# I2C_Shield.net
KiCad netlist of a schematic drawn in EAGLE
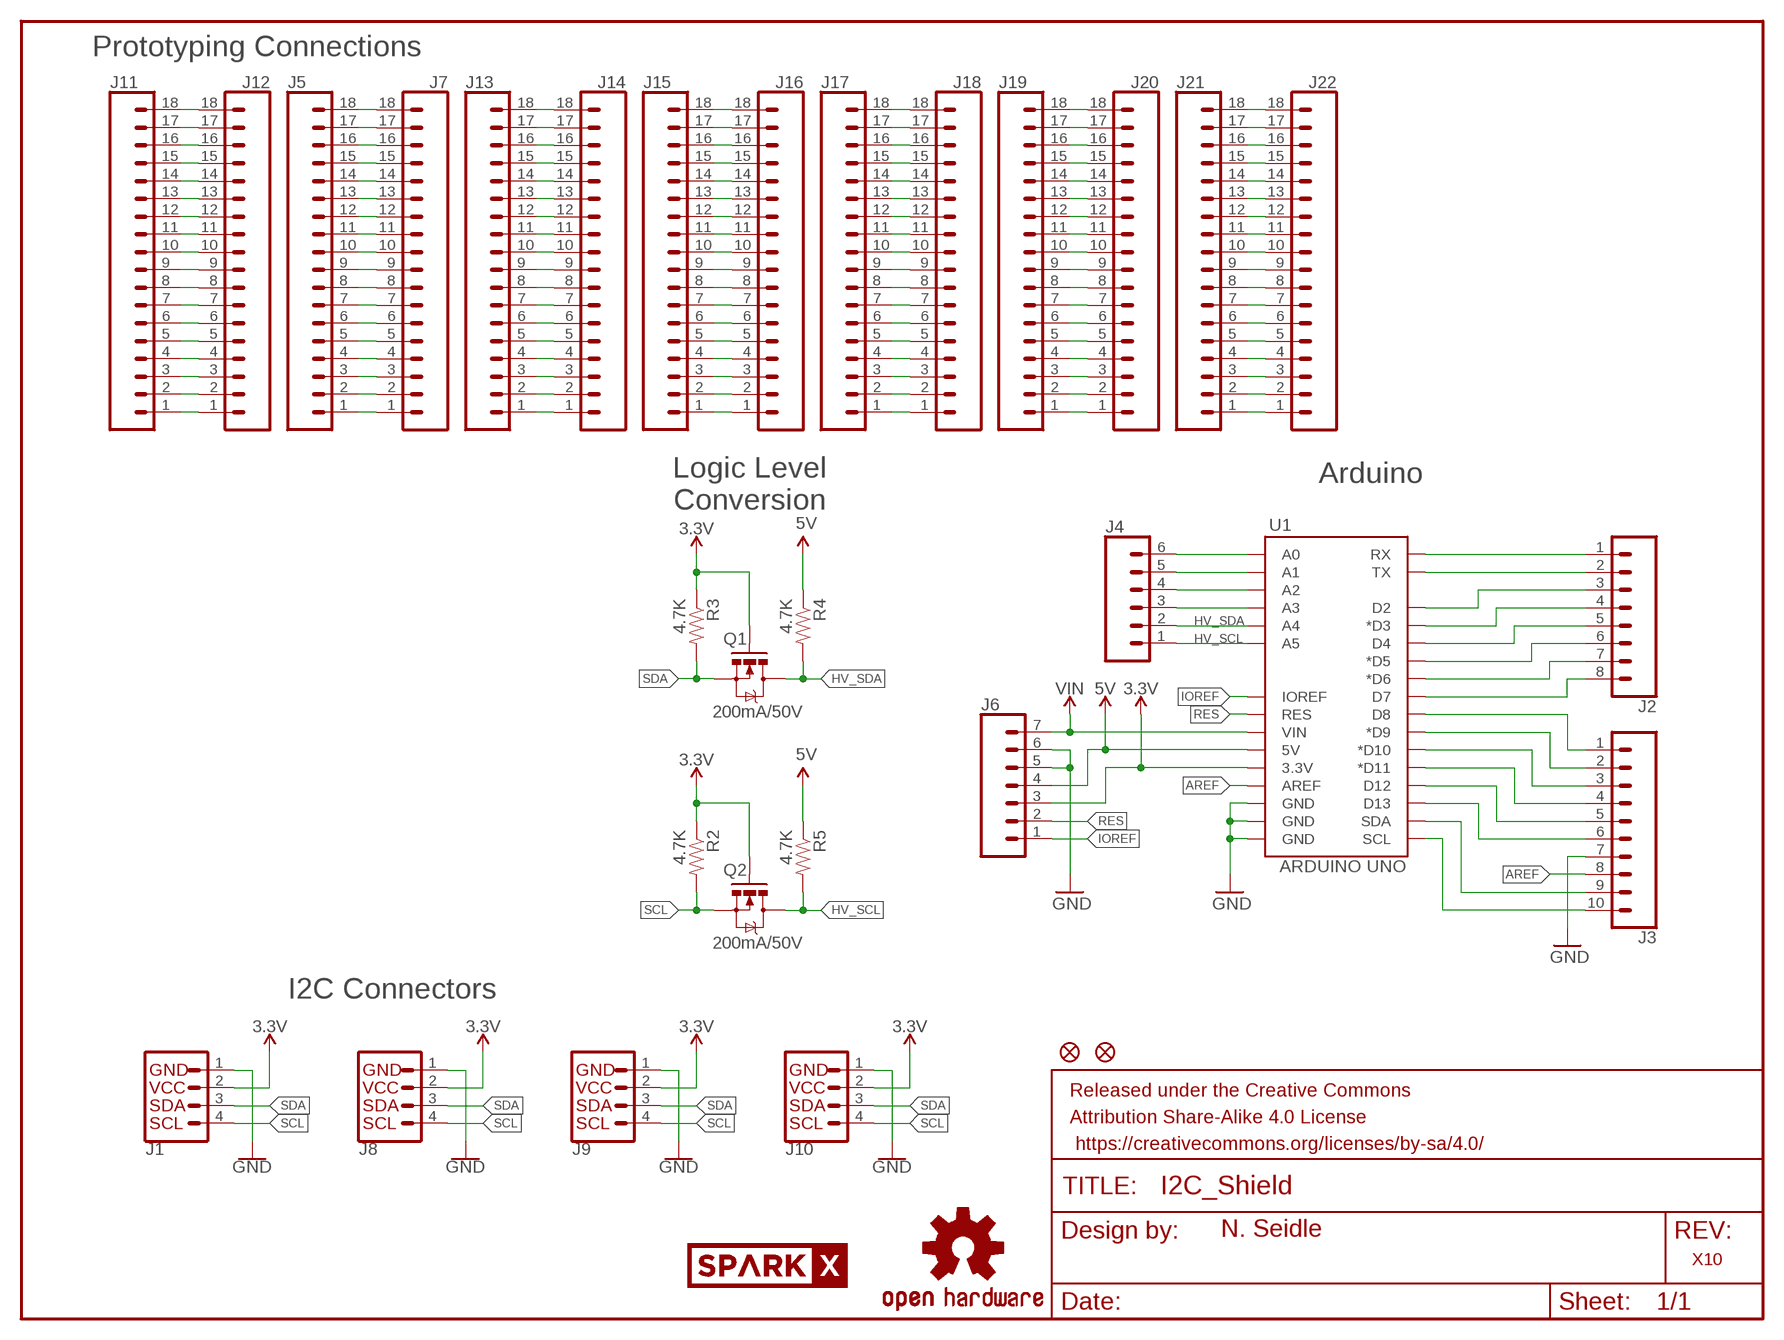
[diagram p0: schematic, sheet 1]

(export (version "E")
  (design (tool "Eeschema 10.0.6"))
  (components
    (comp (ref "FD1")
      (value "FIDUCIAL1X2")
      (footprint "eagle-import:FIDUCIAL-1X2")
      (libsource (lib "eagle-import") (part "FIDUCIAL1X2"))
    )
    (comp (ref "FD2")
      (value "FIDUCIAL1X2")
      (footprint "eagle-import:FIDUCIAL-1X2")
      (libsource (lib "eagle-import") (part "FIDUCIAL1X2"))
    )
    (comp (ref "FRAME1")
      (value "FRAME-LETTER")
      (footprint "eagle-import:CREATIVE_COMMONS")
      (libsource (lib "eagle-import") (part "FRAME-LETTER"))
    )
    (comp (ref "J1")
      (value "I2C_STANDARDJS-1MM")
      (footprint "eagle-import:1X04_1MM_RA")
      (libsource (lib "eagle-import") (part "I2C_STANDARDJS-1MM"))
    )
    (comp (ref "J2")
      (value "CONN_08NO_SILK_FEMALE_PTH")
      (footprint "eagle-import:1X08_NO_SILK")
      (libsource (lib "eagle-import") (part "CONN_08NO_SILK_FEMALE_PTH"))
    )
    (comp (ref "J3")
      (value "CONN_10NO_SILK_PTH_FEMALE")
      (footprint "eagle-import:1X10_NO_SILK")
      (libsource (lib "eagle-import") (part "CONN_10NO_SILK_PTH_FEMALE"))
    )
    (comp (ref "J4")
      (value "CONN_06NO_SILK_FEMALE_PTH")
      (footprint "eagle-import:1X06_NO_SILK")
      (libsource (lib "eagle-import") (part "CONN_06NO_SILK_FEMALE_PTH"))
    )
    (comp (ref "J5")
      (value "CONN_18NO_SILK")
      (footprint "eagle-import:1X18_NO_SILK")
      (libsource (lib "eagle-import") (part "CONN_18NO_SILK"))
    )
    (comp (ref "J6")
      (value "CONN_07NO_SILK")
      (footprint "eagle-import:1X07_NO_SILK")
      (libsource (lib "eagle-import") (part "CONN_07NO_SILK"))
    )
    (comp (ref "J7")
      (value "CONN_18NO_SILK")
      (footprint "eagle-import:1X18_NO_SILK")
      (libsource (lib "eagle-import") (part "CONN_18NO_SILK"))
    )
    (comp (ref "J8")
      (value "I2C_STANDARDJS-1MM")
      (footprint "eagle-import:1X04_1MM_RA")
      (libsource (lib "eagle-import") (part "I2C_STANDARDJS-1MM"))
    )
    (comp (ref "J9")
      (value "I2C_STANDARDJS-1MM")
      (footprint "eagle-import:1X04_1MM_RA")
      (libsource (lib "eagle-import") (part "I2C_STANDARDJS-1MM"))
    )
    (comp (ref "J10")
      (value "I2C_STANDARDJS-1MM")
      (footprint "eagle-import:1X04_1MM_RA")
      (libsource (lib "eagle-import") (part "I2C_STANDARDJS-1MM"))
    )
    (comp (ref "J11")
      (value "CONN_18NO_SILK")
      (footprint "eagle-import:1X18_NO_SILK")
      (libsource (lib "eagle-import") (part "CONN_18NO_SILK"))
    )
    (comp (ref "J12")
      (value "CONN_18NO_SILK")
      (footprint "eagle-import:1X18_NO_SILK")
      (libsource (lib "eagle-import") (part "CONN_18NO_SILK"))
    )
    (comp (ref "J13")
      (value "CONN_18NO_SILK")
      (footprint "eagle-import:1X18_NO_SILK")
      (libsource (lib "eagle-import") (part "CONN_18NO_SILK"))
    )
    (comp (ref "J14")
      (value "CONN_18NO_SILK")
      (footprint "eagle-import:1X18_NO_SILK")
      (libsource (lib "eagle-import") (part "CONN_18NO_SILK"))
    )
    (comp (ref "J15")
      (value "CONN_18NO_SILK")
      (footprint "eagle-import:1X18_NO_SILK")
      (libsource (lib "eagle-import") (part "CONN_18NO_SILK"))
    )
    (comp (ref "J16")
      (value "CONN_18NO_SILK")
      (footprint "eagle-import:1X18_NO_SILK")
      (libsource (lib "eagle-import") (part "CONN_18NO_SILK"))
    )
    (comp (ref "J17")
      (value "CONN_18NO_SILK")
      (footprint "eagle-import:1X18_NO_SILK")
      (libsource (lib "eagle-import") (part "CONN_18NO_SILK"))
    )
    (comp (ref "J18")
      (value "CONN_18NO_SILK")
      (footprint "eagle-import:1X18_NO_SILK")
      (libsource (lib "eagle-import") (part "CONN_18NO_SILK"))
    )
    (comp (ref "J19")
      (value "CONN_18NO_SILK")
      (footprint "eagle-import:1X18_NO_SILK")
      (libsource (lib "eagle-import") (part "CONN_18NO_SILK"))
    )
    (comp (ref "J20")
      (value "CONN_18NO_SILK")
      (footprint "eagle-import:1X18_NO_SILK")
      (libsource (lib "eagle-import") (part "CONN_18NO_SILK"))
    )
    (comp (ref "J21")
      (value "CONN_18NO_SILK")
      (footprint "eagle-import:1X18_NO_SILK")
      (libsource (lib "eagle-import") (part "CONN_18NO_SILK"))
    )
    (comp (ref "J22")
      (value "CONN_18NO_SILK")
      (footprint "eagle-import:1X18_NO_SILK")
      (libsource (lib "eagle-import") (part "CONN_18NO_SILK"))
    )
    (comp (ref "LOGO1")
      (value "OSHW-LOGOMINI")
      (footprint "eagle-import:OSHW-LOGO-MINI")
      (libsource (lib "eagle-import") (part "OSHW-LOGOMINI"))
    )
    (comp (ref "Q1")
      (value "200mA/50V")
      (footprint "eagle-import:SOT23-3")
      (libsource (lib "eagle-import") (part "MOSFET-NCHANNELBSS138"))
    )
    (comp (ref "Q2")
      (value "200mA/50V")
      (footprint "eagle-import:SOT23-3")
      (libsource (lib "eagle-import") (part "MOSFET-NCHANNELBSS138"))
    )
    (comp (ref "R2")
      (value "4.7K")
      (footprint "eagle-import:0603-RES")
      (libsource (lib "eagle-import") (part "4.7KOHM-1/10W-1%(0603)"))
    )
    (comp (ref "R3")
      (value "4.7K")
      (footprint "eagle-import:0603-RES")
      (libsource (lib "eagle-import") (part "4.7KOHM-1/10W-1%(0603)"))
    )
    (comp (ref "R4")
      (value "4.7K")
      (footprint "eagle-import:0603-RES")
      (libsource (lib "eagle-import") (part "4.7KOHM-1/10W-1%(0603)"))
    )
    (comp (ref "R5")
      (value "4.7K")
      (footprint "eagle-import:0603-RES")
      (libsource (lib "eagle-import") (part "4.7KOHM-1/10W-1%(0603)"))
    )
    (comp (ref "U$1")
      (value "SPARKX-LOGO3")
      (footprint "eagle-import:SPARKX-SMALL")
      (libsource (lib "eagle-import") (part "SPARKX-LOGO3"))
    )
    (comp (ref "U$2")
      (value "SPARKX-LOGO5")
      (footprint "eagle-import:SPARKX-LARGE")
      (libsource (lib "eagle-import") (part "SPARKX-LOGO5"))
    )
    (comp (ref "U1")
      (value "ARDUINO UNO")
      (footprint "eagle-import:UNO_R3_SHIELD_NOLABELS")
      (libsource (lib "eagle-import") (part "ARDUINO_R3_SHIELDNOLABELS"))
    )
  )
  (nets
    (net (code "1") (name "3.3V") (class "Default")
      (node (ref "J1") (pin "2") (pinfunction "VCC_2") (pintype "power_in"))
      (node (ref "J10") (pin "2") (pinfunction "VCC_2") (pintype "power_in"))
      (node (ref "J6") (pin "3") (pinfunction "3_3") (pintype "passive"))
      (node (ref "J8") (pin "2") (pinfunction "VCC_2") (pintype "power_in"))
      (node (ref "J9") (pin "2") (pinfunction "VCC_2") (pintype "power_in"))
      (node (ref "Q1") (pin "1") (pinfunction "G_1") (pintype "passive"))
      (node (ref "Q2") (pin "1") (pinfunction "G_1") (pintype "passive"))
      (node (ref "R2") (pin "1") (pinfunction "1_1") (pintype "passive"))
      (node (ref "R3") (pin "1") (pinfunction "1_1") (pintype "passive"))
      (node (ref "U1") (pin "3.3V") (pinfunction "3.3V_3.3V") (pintype "bidirectional"))
    )
    (net (code "2") (name "5V") (class "Default")
      (node (ref "J6") (pin "4") (pinfunction "4_4") (pintype "passive"))
      (node (ref "R4") (pin "1") (pinfunction "1_1") (pintype "passive"))
      (node (ref "R5") (pin "1") (pinfunction "1_1") (pintype "passive"))
      (node (ref "U1") (pin "5V") (pinfunction "5V_5V") (pintype "bidirectional"))
    )
    (net (code "3") (name "AREF") (class "Default")
      (node (ref "J3") (pin "8") (pinfunction "8_8") (pintype "passive"))
      (node (ref "U1") (pin "AREF") (pinfunction "AREF_AREF") (pintype "bidirectional"))
    )
    (net (code "4") (name "GND") (class "Default")
      (node (ref "J1") (pin "1") (pinfunction "GND_1") (pintype "power_in"))
      (node (ref "J10") (pin "1") (pinfunction "GND_1") (pintype "power_in"))
      (node (ref "J3") (pin "7") (pinfunction "7_7") (pintype "passive"))
      (node (ref "J6") (pin "5") (pinfunction "5_5") (pintype "passive"))
      (node (ref "J6") (pin "6") (pinfunction "6_6") (pintype "passive"))
      (node (ref "J8") (pin "1") (pinfunction "GND_1") (pintype "power_in"))
      (node (ref "J9") (pin "1") (pinfunction "GND_1") (pintype "power_in"))
      (node (ref "U1") (pin "GND@0") (pinfunction "GND_GND@0") (pintype "bidirectional"))
      (node (ref "U1") (pin "GND@1") (pinfunction "GND_GND@1") (pintype "bidirectional"))
      (node (ref "U1") (pin "GND@2") (pinfunction "GND_GND@2") (pintype "bidirectional"))
    )
    (net (code "5") (name "HV_SCL") (class "Default")
      (node (ref "J4") (pin "1") (pinfunction "1_1") (pintype "passive"))
      (node (ref "Q2") (pin "3") (pinfunction "D_3") (pintype "passive"))
      (node (ref "R5") (pin "2") (pinfunction "2_2") (pintype "passive"))
      (node (ref "U1") (pin "A5") (pinfunction "A5_A5") (pintype "bidirectional"))
    )
    (net (code "6") (name "HV_SDA") (class "Default")
      (node (ref "J4") (pin "2") (pinfunction "2_2") (pintype "passive"))
      (node (ref "Q1") (pin "3") (pinfunction "D_3") (pintype "passive"))
      (node (ref "R4") (pin "2") (pinfunction "2_2") (pintype "passive"))
      (node (ref "U1") (pin "A4") (pinfunction "A4_A4") (pintype "bidirectional"))
    )
    (net (code "7") (name "IOREF") (class "Default")
      (node (ref "J6") (pin "1") (pinfunction "1_1") (pintype "passive"))
      (node (ref "U1") (pin "IOREF") (pinfunction "IOREF_IOREF") (pintype "bidirectional"))
    )
    (net (code "8") (name "Net-(J2-Pad1)") (class "Default")
      (node (ref "J2") (pin "1") (pinfunction "1_1") (pintype "passive"))
      (node (ref "U1") (pin "RX") (pinfunction "RX_RX") (pintype "bidirectional"))
    )
    (net (code "9") (name "Net-(J2-Pad2)") (class "Default")
      (node (ref "J2") (pin "2") (pinfunction "2_2") (pintype "passive"))
      (node (ref "U1") (pin "TX") (pinfunction "TX_TX") (pintype "bidirectional"))
    )
    (net (code "10") (name "Net-(J2-Pad3)") (class "Default")
      (node (ref "J2") (pin "3") (pinfunction "3_3") (pintype "passive"))
      (node (ref "U1") (pin "D2") (pinfunction "D2_D2") (pintype "bidirectional"))
    )
    (net (code "11") (name "Net-(J2-Pad5)") (class "Default")
      (node (ref "J2") (pin "5") (pinfunction "5_5") (pintype "passive"))
      (node (ref "U1") (pin "D4") (pinfunction "D4_D4") (pintype "bidirectional"))
    )
    (net (code "12") (name "Net-(J2-Pad8)") (class "Default")
      (node (ref "J2") (pin "8") (pinfunction "8_8") (pintype "passive"))
      (node (ref "U1") (pin "D7") (pinfunction "D7_D7") (pintype "bidirectional"))
    )
    (net (code "13") (name "Net-(J3-Pad1)") (class "Default")
      (node (ref "J3") (pin "1") (pinfunction "1_1") (pintype "passive"))
      (node (ref "U1") (pin "D8") (pinfunction "D8_D8") (pintype "bidirectional"))
    )
    (net (code "14") (name "Net-(J3-Pad5)") (class "Default")
      (node (ref "J3") (pin "5") (pinfunction "5_5") (pintype "passive"))
      (node (ref "U1") (pin "D12") (pinfunction "D12_D12") (pintype "bidirectional"))
    )
    (net (code "15") (name "Net-(J3-Pad6)") (class "Default")
      (node (ref "J3") (pin "6") (pinfunction "6_6") (pintype "passive"))
      (node (ref "U1") (pin "D13") (pinfunction "D13_D13") (pintype "bidirectional"))
    )
    (net (code "16") (name "Net-(J3-Pad9)") (class "Default")
      (node (ref "J3") (pin "9") (pinfunction "9_9") (pintype "passive"))
      (node (ref "U1") (pin "SDA") (pinfunction "SDA_SDA") (pintype "bidirectional"))
    )
    (net (code "17") (name "Net-(J3-Pad10)") (class "Default")
      (node (ref "J3") (pin "10") (pinfunction "10_10") (pintype "passive"))
      (node (ref "U1") (pin "SCL") (pinfunction "SCL_SCL") (pintype "bidirectional"))
    )
    (net (code "18") (name "Net-(J4-Pad3)") (class "Default")
      (node (ref "J4") (pin "3") (pinfunction "3_3") (pintype "passive"))
      (node (ref "U1") (pin "A3") (pinfunction "A3_A3") (pintype "bidirectional"))
    )
    (net (code "19") (name "Net-(J4-Pad4)") (class "Default")
      (node (ref "J4") (pin "4") (pinfunction "4_4") (pintype "passive"))
      (node (ref "U1") (pin "A2") (pinfunction "A2_A2") (pintype "bidirectional"))
    )
    (net (code "20") (name "Net-(J4-Pad5)") (class "Default")
      (node (ref "J4") (pin "5") (pinfunction "5_5") (pintype "passive"))
      (node (ref "U1") (pin "A1") (pinfunction "A1_A1") (pintype "bidirectional"))
    )
    (net (code "21") (name "Net-(J4-Pad6)") (class "Default")
      (node (ref "J4") (pin "6") (pinfunction "6_6") (pintype "passive"))
      (node (ref "U1") (pin "A0") (pinfunction "A0_A0") (pintype "bidirectional"))
    )
    (net (code "22") (name "Net-(J5-Pad1)") (class "Default")
      (node (ref "J5") (pin "1") (pinfunction "1_1") (pintype "passive"))
      (node (ref "J7") (pin "1") (pinfunction "1_1") (pintype "passive"))
    )
    (net (code "23") (name "Net-(J5-Pad2)") (class "Default")
      (node (ref "J5") (pin "2") (pinfunction "2_2") (pintype "passive"))
      (node (ref "J7") (pin "2") (pinfunction "2_2") (pintype "passive"))
    )
    (net (code "24") (name "Net-(J5-Pad3)") (class "Default")
      (node (ref "J5") (pin "3") (pinfunction "3_3") (pintype "passive"))
      (node (ref "J7") (pin "3") (pinfunction "3_3") (pintype "passive"))
    )
    (net (code "25") (name "Net-(J5-Pad4)") (class "Default")
      (node (ref "J5") (pin "4") (pinfunction "4_4") (pintype "passive"))
      (node (ref "J7") (pin "4") (pinfunction "4_4") (pintype "passive"))
    )
    (net (code "26") (name "Net-(J5-Pad5)") (class "Default")
      (node (ref "J5") (pin "5") (pinfunction "5_5") (pintype "passive"))
      (node (ref "J7") (pin "5") (pinfunction "5_5") (pintype "passive"))
    )
    (net (code "27") (name "Net-(J5-Pad6)") (class "Default")
      (node (ref "J5") (pin "6") (pinfunction "6_6") (pintype "passive"))
      (node (ref "J7") (pin "6") (pinfunction "6_6") (pintype "passive"))
    )
    (net (code "28") (name "Net-(J5-Pad7)") (class "Default")
      (node (ref "J5") (pin "7") (pinfunction "7_7") (pintype "passive"))
      (node (ref "J7") (pin "7") (pinfunction "7_7") (pintype "passive"))
    )
    (net (code "29") (name "Net-(J5-Pad8)") (class "Default")
      (node (ref "J5") (pin "8") (pinfunction "8_8") (pintype "passive"))
      (node (ref "J7") (pin "8") (pinfunction "8_8") (pintype "passive"))
    )
    (net (code "30") (name "Net-(J5-Pad9)") (class "Default")
      (node (ref "J5") (pin "9") (pinfunction "9_9") (pintype "passive"))
      (node (ref "J7") (pin "9") (pinfunction "9_9") (pintype "passive"))
    )
    (net (code "31") (name "Net-(J5-Pad10)") (class "Default")
      (node (ref "J5") (pin "10") (pinfunction "10_10") (pintype "passive"))
      (node (ref "J7") (pin "10") (pinfunction "10_10") (pintype "passive"))
    )
    (net (code "32") (name "Net-(J5-Pad11)") (class "Default")
      (node (ref "J5") (pin "11") (pinfunction "11_11") (pintype "passive"))
      (node (ref "J7") (pin "11") (pinfunction "11_11") (pintype "passive"))
    )
    (net (code "33") (name "Net-(J5-Pad12)") (class "Default")
      (node (ref "J5") (pin "12") (pinfunction "12_12") (pintype "passive"))
      (node (ref "J7") (pin "12") (pinfunction "12_12") (pintype "passive"))
    )
    (net (code "34") (name "Net-(J5-Pad13)") (class "Default")
      (node (ref "J5") (pin "13") (pinfunction "13_13") (pintype "passive"))
      (node (ref "J7") (pin "13") (pinfunction "13_13") (pintype "passive"))
    )
    (net (code "35") (name "Net-(J5-Pad14)") (class "Default")
      (node (ref "J5") (pin "14") (pinfunction "14_14") (pintype "passive"))
      (node (ref "J7") (pin "14") (pinfunction "14_14") (pintype "passive"))
    )
    (net (code "36") (name "Net-(J5-Pad15)") (class "Default")
      (node (ref "J5") (pin "15") (pinfunction "15_15") (pintype "passive"))
      (node (ref "J7") (pin "15") (pinfunction "15_15") (pintype "passive"))
    )
    (net (code "37") (name "Net-(J5-Pad16)") (class "Default")
      (node (ref "J5") (pin "16") (pinfunction "16_16") (pintype "passive"))
      (node (ref "J7") (pin "16") (pinfunction "16_16") (pintype "passive"))
    )
    (net (code "38") (name "Net-(J5-Pad17)") (class "Default")
      (node (ref "J5") (pin "17") (pinfunction "17_17") (pintype "passive"))
      (node (ref "J7") (pin "17") (pinfunction "17_17") (pintype "passive"))
    )
    (net (code "39") (name "Net-(J5-Pad18)") (class "Default")
      (node (ref "J5") (pin "18") (pinfunction "18_18") (pintype "passive"))
      (node (ref "J7") (pin "18") (pinfunction "18_18") (pintype "passive"))
    )
    (net (code "40") (name "Net-(J11-Pad1)") (class "Default")
      (node (ref "J11") (pin "1") (pinfunction "1_1") (pintype "passive"))
      (node (ref "J12") (pin "1") (pinfunction "1_1") (pintype "passive"))
    )
    (net (code "41") (name "Net-(J11-Pad2)") (class "Default")
      (node (ref "J11") (pin "2") (pinfunction "2_2") (pintype "passive"))
      (node (ref "J12") (pin "2") (pinfunction "2_2") (pintype "passive"))
    )
    (net (code "42") (name "Net-(J11-Pad3)") (class "Default")
      (node (ref "J11") (pin "3") (pinfunction "3_3") (pintype "passive"))
      (node (ref "J12") (pin "3") (pinfunction "3_3") (pintype "passive"))
    )
    (net (code "43") (name "Net-(J11-Pad4)") (class "Default")
      (node (ref "J11") (pin "4") (pinfunction "4_4") (pintype "passive"))
      (node (ref "J12") (pin "4") (pinfunction "4_4") (pintype "passive"))
    )
    (net (code "44") (name "Net-(J11-Pad5)") (class "Default")
      (node (ref "J11") (pin "5") (pinfunction "5_5") (pintype "passive"))
      (node (ref "J12") (pin "5") (pinfunction "5_5") (pintype "passive"))
    )
    (net (code "45") (name "Net-(J11-Pad6)") (class "Default")
      (node (ref "J11") (pin "6") (pinfunction "6_6") (pintype "passive"))
      (node (ref "J12") (pin "6") (pinfunction "6_6") (pintype "passive"))
    )
    (net (code "46") (name "Net-(J11-Pad7)") (class "Default")
      (node (ref "J11") (pin "7") (pinfunction "7_7") (pintype "passive"))
      (node (ref "J12") (pin "7") (pinfunction "7_7") (pintype "passive"))
    )
    (net (code "47") (name "Net-(J11-Pad8)") (class "Default")
      (node (ref "J11") (pin "8") (pinfunction "8_8") (pintype "passive"))
      (node (ref "J12") (pin "8") (pinfunction "8_8") (pintype "passive"))
    )
    (net (code "48") (name "Net-(J11-Pad9)") (class "Default")
      (node (ref "J11") (pin "9") (pinfunction "9_9") (pintype "passive"))
      (node (ref "J12") (pin "9") (pinfunction "9_9") (pintype "passive"))
    )
    (net (code "49") (name "Net-(J11-Pad10)") (class "Default")
      (node (ref "J11") (pin "10") (pinfunction "10_10") (pintype "passive"))
      (node (ref "J12") (pin "10") (pinfunction "10_10") (pintype "passive"))
    )
    (net (code "50") (name "Net-(J11-Pad11)") (class "Default")
      (node (ref "J11") (pin "11") (pinfunction "11_11") (pintype "passive"))
      (node (ref "J12") (pin "11") (pinfunction "11_11") (pintype "passive"))
    )
    (net (code "51") (name "Net-(J11-Pad12)") (class "Default")
      (node (ref "J11") (pin "12") (pinfunction "12_12") (pintype "passive"))
      (node (ref "J12") (pin "12") (pinfunction "12_12") (pintype "passive"))
    )
    (net (code "52") (name "Net-(J11-Pad13)") (class "Default")
      (node (ref "J11") (pin "13") (pinfunction "13_13") (pintype "passive"))
      (node (ref "J12") (pin "13") (pinfunction "13_13") (pintype "passive"))
    )
    (net (code "53") (name "Net-(J11-Pad14)") (class "Default")
      (node (ref "J11") (pin "14") (pinfunction "14_14") (pintype "passive"))
      (node (ref "J12") (pin "14") (pinfunction "14_14") (pintype "passive"))
    )
    (net (code "54") (name "Net-(J11-Pad15)") (class "Default")
      (node (ref "J11") (pin "15") (pinfunction "15_15") (pintype "passive"))
      (node (ref "J12") (pin "15") (pinfunction "15_15") (pintype "passive"))
    )
    (net (code "55") (name "Net-(J11-Pad16)") (class "Default")
      (node (ref "J11") (pin "16") (pinfunction "16_16") (pintype "passive"))
      (node (ref "J12") (pin "16") (pinfunction "16_16") (pintype "passive"))
    )
    (net (code "56") (name "Net-(J11-Pad17)") (class "Default")
      (node (ref "J11") (pin "17") (pinfunction "17_17") (pintype "passive"))
      (node (ref "J12") (pin "17") (pinfunction "17_17") (pintype "passive"))
    )
    (net (code "57") (name "Net-(J11-Pad18)") (class "Default")
      (node (ref "J11") (pin "18") (pinfunction "18_18") (pintype "passive"))
      (node (ref "J12") (pin "18") (pinfunction "18_18") (pintype "passive"))
    )
    (net (code "58") (name "Net-(J13-Pad1)") (class "Default")
      (node (ref "J13") (pin "1") (pinfunction "1_1") (pintype "passive"))
      (node (ref "J14") (pin "1") (pinfunction "1_1") (pintype "passive"))
    )
    (net (code "59") (name "Net-(J13-Pad2)") (class "Default")
      (node (ref "J13") (pin "2") (pinfunction "2_2") (pintype "passive"))
      (node (ref "J14") (pin "2") (pinfunction "2_2") (pintype "passive"))
    )
    (net (code "60") (name "Net-(J13-Pad3)") (class "Default")
      (node (ref "J13") (pin "3") (pinfunction "3_3") (pintype "passive"))
      (node (ref "J14") (pin "3") (pinfunction "3_3") (pintype "passive"))
    )
    (net (code "61") (name "Net-(J13-Pad4)") (class "Default")
      (node (ref "J13") (pin "4") (pinfunction "4_4") (pintype "passive"))
      (node (ref "J14") (pin "4") (pinfunction "4_4") (pintype "passive"))
    )
    (net (code "62") (name "Net-(J13-Pad5)") (class "Default")
      (node (ref "J13") (pin "5") (pinfunction "5_5") (pintype "passive"))
      (node (ref "J14") (pin "5") (pinfunction "5_5") (pintype "passive"))
    )
    (net (code "63") (name "Net-(J13-Pad6)") (class "Default")
      (node (ref "J13") (pin "6") (pinfunction "6_6") (pintype "passive"))
      (node (ref "J14") (pin "6") (pinfunction "6_6") (pintype "passive"))
    )
    (net (code "64") (name "Net-(J13-Pad7)") (class "Default")
      (node (ref "J13") (pin "7") (pinfunction "7_7") (pintype "passive"))
      (node (ref "J14") (pin "7") (pinfunction "7_7") (pintype "passive"))
    )
    (net (code "65") (name "Net-(J13-Pad8)") (class "Default")
      (node (ref "J13") (pin "8") (pinfunction "8_8") (pintype "passive"))
      (node (ref "J14") (pin "8") (pinfunction "8_8") (pintype "passive"))
    )
    (net (code "66") (name "Net-(J13-Pad9)") (class "Default")
      (node (ref "J13") (pin "9") (pinfunction "9_9") (pintype "passive"))
      (node (ref "J14") (pin "9") (pinfunction "9_9") (pintype "passive"))
    )
    (net (code "67") (name "Net-(J13-Pad10)") (class "Default")
      (node (ref "J13") (pin "10") (pinfunction "10_10") (pintype "passive"))
      (node (ref "J14") (pin "10") (pinfunction "10_10") (pintype "passive"))
    )
    (net (code "68") (name "Net-(J13-Pad11)") (class "Default")
      (node (ref "J13") (pin "11") (pinfunction "11_11") (pintype "passive"))
      (node (ref "J14") (pin "11") (pinfunction "11_11") (pintype "passive"))
    )
    (net (code "69") (name "Net-(J13-Pad12)") (class "Default")
      (node (ref "J13") (pin "12") (pinfunction "12_12") (pintype "passive"))
      (node (ref "J14") (pin "12") (pinfunction "12_12") (pintype "passive"))
    )
    (net (code "70") (name "Net-(J13-Pad13)") (class "Default")
      (node (ref "J13") (pin "13") (pinfunction "13_13") (pintype "passive"))
      (node (ref "J14") (pin "13") (pinfunction "13_13") (pintype "passive"))
    )
    (net (code "71") (name "Net-(J13-Pad14)") (class "Default")
      (node (ref "J13") (pin "14") (pinfunction "14_14") (pintype "passive"))
      (node (ref "J14") (pin "14") (pinfunction "14_14") (pintype "passive"))
    )
    (net (code "72") (name "Net-(J13-Pad15)") (class "Default")
      (node (ref "J13") (pin "15") (pinfunction "15_15") (pintype "passive"))
      (node (ref "J14") (pin "15") (pinfunction "15_15") (pintype "passive"))
    )
    (net (code "73") (name "Net-(J13-Pad16)") (class "Default")
      (node (ref "J13") (pin "16") (pinfunction "16_16") (pintype "passive"))
      (node (ref "J14") (pin "16") (pinfunction "16_16") (pintype "passive"))
    )
    (net (code "74") (name "Net-(J13-Pad17)") (class "Default")
      (node (ref "J13") (pin "17") (pinfunction "17_17") (pintype "passive"))
      (node (ref "J14") (pin "17") (pinfunction "17_17") (pintype "passive"))
    )
    (net (code "75") (name "Net-(J13-Pad18)") (class "Default")
      (node (ref "J13") (pin "18") (pinfunction "18_18") (pintype "passive"))
      (node (ref "J14") (pin "18") (pinfunction "18_18") (pintype "passive"))
    )
    (net (code "76") (name "Net-(J15-Pad1)") (class "Default")
      (node (ref "J15") (pin "1") (pinfunction "1_1") (pintype "passive"))
      (node (ref "J16") (pin "1") (pinfunction "1_1") (pintype "passive"))
    )
    (net (code "77") (name "Net-(J15-Pad2)") (class "Default")
      (node (ref "J15") (pin "2") (pinfunction "2_2") (pintype "passive"))
      (node (ref "J16") (pin "2") (pinfunction "2_2") (pintype "passive"))
    )
    (net (code "78") (name "Net-(J15-Pad3)") (class "Default")
      (node (ref "J15") (pin "3") (pinfunction "3_3") (pintype "passive"))
      (node (ref "J16") (pin "3") (pinfunction "3_3") (pintype "passive"))
    )
    (net (code "79") (name "Net-(J15-Pad4)") (class "Default")
      (node (ref "J15") (pin "4") (pinfunction "4_4") (pintype "passive"))
      (node (ref "J16") (pin "4") (pinfunction "4_4") (pintype "passive"))
    )
    (net (code "80") (name "Net-(J15-Pad5)") (class "Default")
      (node (ref "J15") (pin "5") (pinfunction "5_5") (pintype "passive"))
      (node (ref "J16") (pin "5") (pinfunction "5_5") (pintype "passive"))
    )
    (net (code "81") (name "Net-(J15-Pad6)") (class "Default")
      (node (ref "J15") (pin "6") (pinfunction "6_6") (pintype "passive"))
      (node (ref "J16") (pin "6") (pinfunction "6_6") (pintype "passive"))
    )
    (net (code "82") (name "Net-(J15-Pad7)") (class "Default")
      (node (ref "J15") (pin "7") (pinfunction "7_7") (pintype "passive"))
      (node (ref "J16") (pin "7") (pinfunction "7_7") (pintype "passive"))
    )
    (net (code "83") (name "Net-(J15-Pad8)") (class "Default")
      (node (ref "J15") (pin "8") (pinfunction "8_8") (pintype "passive"))
      (node (ref "J16") (pin "8") (pinfunction "8_8") (pintype "passive"))
    )
    (net (code "84") (name "Net-(J15-Pad9)") (class "Default")
      (node (ref "J15") (pin "9") (pinfunction "9_9") (pintype "passive"))
      (node (ref "J16") (pin "9") (pinfunction "9_9") (pintype "passive"))
    )
    (net (code "85") (name "Net-(J15-Pad10)") (class "Default")
      (node (ref "J15") (pin "10") (pinfunction "10_10") (pintype "passive"))
      (node (ref "J16") (pin "10") (pinfunction "10_10") (pintype "passive"))
    )
    (net (code "86") (name "Net-(J15-Pad11)") (class "Default")
      (node (ref "J15") (pin "11") (pinfunction "11_11") (pintype "passive"))
      (node (ref "J16") (pin "11") (pinfunction "11_11") (pintype "passive"))
    )
    (net (code "87") (name "Net-(J15-Pad12)") (class "Default")
      (node (ref "J15") (pin "12") (pinfunction "12_12") (pintype "passive"))
      (node (ref "J16") (pin "12") (pinfunction "12_12") (pintype "passive"))
    )
    (net (code "88") (name "Net-(J15-Pad13)") (class "Default")
      (node (ref "J15") (pin "13") (pinfunction "13_13") (pintype "passive"))
      (node (ref "J16") (pin "13") (pinfunction "13_13") (pintype "passive"))
    )
    (net (code "89") (name "Net-(J15-Pad14)") (class "Default")
      (node (ref "J15") (pin "14") (pinfunction "14_14") (pintype "passive"))
      (node (ref "J16") (pin "14") (pinfunction "14_14") (pintype "passive"))
    )
    (net (code "90") (name "Net-(J15-Pad15)") (class "Default")
      (node (ref "J15") (pin "15") (pinfunction "15_15") (pintype "passive"))
      (node (ref "J16") (pin "15") (pinfunction "15_15") (pintype "passive"))
    )
    (net (code "91") (name "Net-(J15-Pad16)") (class "Default")
      (node (ref "J15") (pin "16") (pinfunction "16_16") (pintype "passive"))
      (node (ref "J16") (pin "16") (pinfunction "16_16") (pintype "passive"))
    )
    (net (code "92") (name "Net-(J15-Pad17)") (class "Default")
      (node (ref "J15") (pin "17") (pinfunction "17_17") (pintype "passive"))
      (node (ref "J16") (pin "17") (pinfunction "17_17") (pintype "passive"))
    )
    (net (code "93") (name "Net-(J15-Pad18)") (class "Default")
      (node (ref "J15") (pin "18") (pinfunction "18_18") (pintype "passive"))
      (node (ref "J16") (pin "18") (pinfunction "18_18") (pintype "passive"))
    )
    (net (code "94") (name "Net-(J17-Pad1)") (class "Default")
      (node (ref "J17") (pin "1") (pinfunction "1_1") (pintype "passive"))
      (node (ref "J18") (pin "1") (pinfunction "1_1") (pintype "passive"))
    )
    (net (code "95") (name "Net-(J17-Pad2)") (class "Default")
      (node (ref "J17") (pin "2") (pinfunction "2_2") (pintype "passive"))
      (node (ref "J18") (pin "2") (pinfunction "2_2") (pintype "passive"))
    )
    (net (code "96") (name "Net-(J17-Pad3)") (class "Default")
      (node (ref "J17") (pin "3") (pinfunction "3_3") (pintype "passive"))
      (node (ref "J18") (pin "3") (pinfunction "3_3") (pintype "passive"))
    )
    (net (code "97") (name "Net-(J17-Pad4)") (class "Default")
      (node (ref "J17") (pin "4") (pinfunction "4_4") (pintype "passive"))
      (node (ref "J18") (pin "4") (pinfunction "4_4") (pintype "passive"))
    )
    (net (code "98") (name "Net-(J17-Pad5)") (class "Default")
      (node (ref "J17") (pin "5") (pinfunction "5_5") (pintype "passive"))
      (node (ref "J18") (pin "5") (pinfunction "5_5") (pintype "passive"))
    )
    (net (code "99") (name "Net-(J17-Pad6)") (class "Default")
      (node (ref "J17") (pin "6") (pinfunction "6_6") (pintype "passive"))
      (node (ref "J18") (pin "6") (pinfunction "6_6") (pintype "passive"))
    )
    (net (code "100") (name "Net-(J17-Pad7)") (class "Default")
      (node (ref "J17") (pin "7") (pinfunction "7_7") (pintype "passive"))
      (node (ref "J18") (pin "7") (pinfunction "7_7") (pintype "passive"))
    )
    (net (code "101") (name "Net-(J17-Pad8)") (class "Default")
      (node (ref "J17") (pin "8") (pinfunction "8_8") (pintype "passive"))
      (node (ref "J18") (pin "8") (pinfunction "8_8") (pintype "passive"))
    )
    (net (code "102") (name "Net-(J17-Pad9)") (class "Default")
      (node (ref "J17") (pin "9") (pinfunction "9_9") (pintype "passive"))
      (node (ref "J18") (pin "9") (pinfunction "9_9") (pintype "passive"))
    )
    (net (code "103") (name "Net-(J17-Pad10)") (class "Default")
      (node (ref "J17") (pin "10") (pinfunction "10_10") (pintype "passive"))
      (node (ref "J18") (pin "10") (pinfunction "10_10") (pintype "passive"))
    )
    (net (code "104") (name "Net-(J17-Pad11)") (class "Default")
      (node (ref "J17") (pin "11") (pinfunction "11_11") (pintype "passive"))
      (node (ref "J18") (pin "11") (pinfunction "11_11") (pintype "passive"))
    )
    (net (code "105") (name "Net-(J17-Pad12)") (class "Default")
      (node (ref "J17") (pin "12") (pinfunction "12_12") (pintype "passive"))
      (node (ref "J18") (pin "12") (pinfunction "12_12") (pintype "passive"))
    )
    (net (code "106") (name "Net-(J17-Pad13)") (class "Default")
      (node (ref "J17") (pin "13") (pinfunction "13_13") (pintype "passive"))
      (node (ref "J18") (pin "13") (pinfunction "13_13") (pintype "passive"))
    )
    (net (code "107") (name "Net-(J17-Pad14)") (class "Default")
      (node (ref "J17") (pin "14") (pinfunction "14_14") (pintype "passive"))
      (node (ref "J18") (pin "14") (pinfunction "14_14") (pintype "passive"))
    )
    (net (code "108") (name "Net-(J17-Pad15)") (class "Default")
      (node (ref "J17") (pin "15") (pinfunction "15_15") (pintype "passive"))
      (node (ref "J18") (pin "15") (pinfunction "15_15") (pintype "passive"))
    )
    (net (code "109") (name "Net-(J17-Pad16)") (class "Default")
      (node (ref "J17") (pin "16") (pinfunction "16_16") (pintype "passive"))
      (node (ref "J18") (pin "16") (pinfunction "16_16") (pintype "passive"))
    )
    (net (code "110") (name "Net-(J17-Pad17)") (class "Default")
      (node (ref "J17") (pin "17") (pinfunction "17_17") (pintype "passive"))
      (node (ref "J18") (pin "17") (pinfunction "17_17") (pintype "passive"))
    )
    (net (code "111") (name "Net-(J17-Pad18)") (class "Default")
      (node (ref "J17") (pin "18") (pinfunction "18_18") (pintype "passive"))
      (node (ref "J18") (pin "18") (pinfunction "18_18") (pintype "passive"))
    )
    (net (code "112") (name "Net-(J19-Pad1)") (class "Default")
      (node (ref "J19") (pin "1") (pinfunction "1_1") (pintype "passive"))
      (node (ref "J20") (pin "1") (pinfunction "1_1") (pintype "passive"))
    )
    (net (code "113") (name "Net-(J19-Pad2)") (class "Default")
      (node (ref "J19") (pin "2") (pinfunction "2_2") (pintype "passive"))
      (node (ref "J20") (pin "2") (pinfunction "2_2") (pintype "passive"))
    )
    (net (code "114") (name "Net-(J19-Pad3)") (class "Default")
      (node (ref "J19") (pin "3") (pinfunction "3_3") (pintype "passive"))
      (node (ref "J20") (pin "3") (pinfunction "3_3") (pintype "passive"))
    )
    (net (code "115") (name "Net-(J19-Pad4)") (class "Default")
      (node (ref "J19") (pin "4") (pinfunction "4_4") (pintype "passive"))
      (node (ref "J20") (pin "4") (pinfunction "4_4") (pintype "passive"))
    )
    (net (code "116") (name "Net-(J19-Pad5)") (class "Default")
      (node (ref "J19") (pin "5") (pinfunction "5_5") (pintype "passive"))
      (node (ref "J20") (pin "5") (pinfunction "5_5") (pintype "passive"))
    )
    (net (code "117") (name "Net-(J19-Pad6)") (class "Default")
      (node (ref "J19") (pin "6") (pinfunction "6_6") (pintype "passive"))
      (node (ref "J20") (pin "6") (pinfunction "6_6") (pintype "passive"))
    )
    (net (code "118") (name "Net-(J19-Pad7)") (class "Default")
      (node (ref "J19") (pin "7") (pinfunction "7_7") (pintype "passive"))
      (node (ref "J20") (pin "7") (pinfunction "7_7") (pintype "passive"))
    )
    (net (code "119") (name "Net-(J19-Pad8)") (class "Default")
      (node (ref "J19") (pin "8") (pinfunction "8_8") (pintype "passive"))
      (node (ref "J20") (pin "8") (pinfunction "8_8") (pintype "passive"))
    )
    (net (code "120") (name "Net-(J19-Pad9)") (class "Default")
      (node (ref "J19") (pin "9") (pinfunction "9_9") (pintype "passive"))
      (node (ref "J20") (pin "9") (pinfunction "9_9") (pintype "passive"))
    )
    (net (code "121") (name "Net-(J19-Pad10)") (class "Default")
      (node (ref "J19") (pin "10") (pinfunction "10_10") (pintype "passive"))
      (node (ref "J20") (pin "10") (pinfunction "10_10") (pintype "passive"))
    )
    (net (code "122") (name "Net-(J19-Pad11)") (class "Default")
      (node (ref "J19") (pin "11") (pinfunction "11_11") (pintype "passive"))
      (node (ref "J20") (pin "11") (pinfunction "11_11") (pintype "passive"))
    )
    (net (code "123") (name "Net-(J19-Pad12)") (class "Default")
      (node (ref "J19") (pin "12") (pinfunction "12_12") (pintype "passive"))
      (node (ref "J20") (pin "12") (pinfunction "12_12") (pintype "passive"))
    )
    (net (code "124") (name "Net-(J19-Pad13)") (class "Default")
      (node (ref "J19") (pin "13") (pinfunction "13_13") (pintype "passive"))
      (node (ref "J20") (pin "13") (pinfunction "13_13") (pintype "passive"))
    )
    (net (code "125") (name "Net-(J19-Pad14)") (class "Default")
      (node (ref "J19") (pin "14") (pinfunction "14_14") (pintype "passive"))
      (node (ref "J20") (pin "14") (pinfunction "14_14") (pintype "passive"))
    )
    (net (code "126") (name "Net-(J19-Pad15)") (class "Default")
      (node (ref "J19") (pin "15") (pinfunction "15_15") (pintype "passive"))
      (node (ref "J20") (pin "15") (pinfunction "15_15") (pintype "passive"))
    )
    (net (code "127") (name "Net-(J19-Pad16)") (class "Default")
      (node (ref "J19") (pin "16") (pinfunction "16_16") (pintype "passive"))
      (node (ref "J20") (pin "16") (pinfunction "16_16") (pintype "passive"))
    )
    (net (code "128") (name "Net-(J19-Pad17)") (class "Default")
      (node (ref "J19") (pin "17") (pinfunction "17_17") (pintype "passive"))
      (node (ref "J20") (pin "17") (pinfunction "17_17") (pintype "passive"))
    )
    (net (code "129") (name "Net-(J19-Pad18)") (class "Default")
      (node (ref "J19") (pin "18") (pinfunction "18_18") (pintype "passive"))
      (node (ref "J20") (pin "18") (pinfunction "18_18") (pintype "passive"))
    )
    (net (code "130") (name "Net-(J21-Pad1)") (class "Default")
      (node (ref "J21") (pin "1") (pinfunction "1_1") (pintype "passive"))
      (node (ref "J22") (pin "1") (pinfunction "1_1") (pintype "passive"))
    )
    (net (code "131") (name "Net-(J21-Pad2)") (class "Default")
      (node (ref "J21") (pin "2") (pinfunction "2_2") (pintype "passive"))
      (node (ref "J22") (pin "2") (pinfunction "2_2") (pintype "passive"))
    )
    (net (code "132") (name "Net-(J21-Pad3)") (class "Default")
      (node (ref "J21") (pin "3") (pinfunction "3_3") (pintype "passive"))
      (node (ref "J22") (pin "3") (pinfunction "3_3") (pintype "passive"))
    )
    (net (code "133") (name "Net-(J21-Pad4)") (class "Default")
      (node (ref "J21") (pin "4") (pinfunction "4_4") (pintype "passive"))
      (node (ref "J22") (pin "4") (pinfunction "4_4") (pintype "passive"))
    )
    (net (code "134") (name "Net-(J21-Pad5)") (class "Default")
      (node (ref "J21") (pin "5") (pinfunction "5_5") (pintype "passive"))
      (node (ref "J22") (pin "5") (pinfunction "5_5") (pintype "passive"))
    )
    (net (code "135") (name "Net-(J21-Pad6)") (class "Default")
      (node (ref "J21") (pin "6") (pinfunction "6_6") (pintype "passive"))
      (node (ref "J22") (pin "6") (pinfunction "6_6") (pintype "passive"))
    )
    (net (code "136") (name "Net-(J21-Pad7)") (class "Default")
      (node (ref "J21") (pin "7") (pinfunction "7_7") (pintype "passive"))
      (node (ref "J22") (pin "7") (pinfunction "7_7") (pintype "passive"))
    )
    (net (code "137") (name "Net-(J21-Pad8)") (class "Default")
      (node (ref "J21") (pin "8") (pinfunction "8_8") (pintype "passive"))
      (node (ref "J22") (pin "8") (pinfunction "8_8") (pintype "passive"))
    )
    (net (code "138") (name "Net-(J21-Pad9)") (class "Default")
      (node (ref "J21") (pin "9") (pinfunction "9_9") (pintype "passive"))
      (node (ref "J22") (pin "9") (pinfunction "9_9") (pintype "passive"))
    )
    (net (code "139") (name "Net-(J21-Pad10)") (class "Default")
      (node (ref "J21") (pin "10") (pinfunction "10_10") (pintype "passive"))
      (node (ref "J22") (pin "10") (pinfunction "10_10") (pintype "passive"))
    )
    (net (code "140") (name "Net-(J21-Pad11)") (class "Default")
      (node (ref "J21") (pin "11") (pinfunction "11_11") (pintype "passive"))
      (node (ref "J22") (pin "11") (pinfunction "11_11") (pintype "passive"))
    )
    (net (code "141") (name "Net-(J21-Pad12)") (class "Default")
      (node (ref "J21") (pin "12") (pinfunction "12_12") (pintype "passive"))
      (node (ref "J22") (pin "12") (pinfunction "12_12") (pintype "passive"))
    )
    (net (code "142") (name "Net-(J21-Pad13)") (class "Default")
      (node (ref "J21") (pin "13") (pinfunction "13_13") (pintype "passive"))
      (node (ref "J22") (pin "13") (pinfunction "13_13") (pintype "passive"))
    )
    (net (code "143") (name "Net-(J21-Pad14)") (class "Default")
      (node (ref "J21") (pin "14") (pinfunction "14_14") (pintype "passive"))
      (node (ref "J22") (pin "14") (pinfunction "14_14") (pintype "passive"))
    )
    (net (code "144") (name "Net-(J21-Pad15)") (class "Default")
      (node (ref "J21") (pin "15") (pinfunction "15_15") (pintype "passive"))
      (node (ref "J22") (pin "15") (pinfunction "15_15") (pintype "passive"))
    )
    (net (code "145") (name "Net-(J21-Pad16)") (class "Default")
      (node (ref "J21") (pin "16") (pinfunction "16_16") (pintype "passive"))
      (node (ref "J22") (pin "16") (pinfunction "16_16") (pintype "passive"))
    )
    (net (code "146") (name "Net-(J21-Pad17)") (class "Default")
      (node (ref "J21") (pin "17") (pinfunction "17_17") (pintype "passive"))
      (node (ref "J22") (pin "17") (pinfunction "17_17") (pintype "passive"))
    )
    (net (code "147") (name "Net-(J21-Pad18)") (class "Default")
      (node (ref "J21") (pin "18") (pinfunction "18_18") (pintype "passive"))
      (node (ref "J22") (pin "18") (pinfunction "18_18") (pintype "passive"))
    )
    (net (code "148") (name "Net-(U1-*D3)") (class "Default")
      (node (ref "J2") (pin "4") (pinfunction "4_4") (pintype "passive"))
      (node (ref "U1") (pin "D3") (pinfunction "*D3_D3") (pintype "bidirectional"))
    )
    (net (code "149") (name "Net-(U1-*D5)") (class "Default")
      (node (ref "J2") (pin "6") (pinfunction "6_6") (pintype "passive"))
      (node (ref "U1") (pin "D5") (pinfunction "*D5_D5") (pintype "bidirectional"))
    )
    (net (code "150") (name "Net-(U1-*D6)") (class "Default")
      (node (ref "J2") (pin "7") (pinfunction "7_7") (pintype "passive"))
      (node (ref "U1") (pin "D6") (pinfunction "*D6_D6") (pintype "bidirectional"))
    )
    (net (code "151") (name "Net-(U1-*D9)") (class "Default")
      (node (ref "J3") (pin "2") (pinfunction "2_2") (pintype "passive"))
      (node (ref "U1") (pin "D9") (pinfunction "*D9_D9") (pintype "bidirectional"))
    )
    (net (code "152") (name "Net-(U1-*D10)") (class "Default")
      (node (ref "J3") (pin "3") (pinfunction "3_3") (pintype "passive"))
      (node (ref "U1") (pin "D10") (pinfunction "*D10_D10") (pintype "bidirectional"))
    )
    (net (code "153") (name "Net-(U1-*D11)") (class "Default")
      (node (ref "J3") (pin "4") (pinfunction "4_4") (pintype "passive"))
      (node (ref "U1") (pin "D11") (pinfunction "*D11_D11") (pintype "bidirectional"))
    )
    (net (code "154") (name "RES") (class "Default")
      (node (ref "J6") (pin "2") (pinfunction "2_2") (pintype "passive"))
      (node (ref "U1") (pin "RES") (pinfunction "RES_RES") (pintype "bidirectional"))
    )
    (net (code "155") (name "SCL") (class "Default")
      (node (ref "J1") (pin "4") (pinfunction "SCL_4") (pintype "passive"))
      (node (ref "J10") (pin "4") (pinfunction "SCL_4") (pintype "passive"))
      (node (ref "J8") (pin "4") (pinfunction "SCL_4") (pintype "passive"))
      (node (ref "J9") (pin "4") (pinfunction "SCL_4") (pintype "passive"))
      (node (ref "Q2") (pin "2") (pinfunction "S_2") (pintype "passive"))
      (node (ref "R2") (pin "2") (pinfunction "2_2") (pintype "passive"))
    )
    (net (code "156") (name "SDA") (class "Default")
      (node (ref "J1") (pin "3") (pinfunction "SDA_3") (pintype "passive"))
      (node (ref "J10") (pin "3") (pinfunction "SDA_3") (pintype "passive"))
      (node (ref "J8") (pin "3") (pinfunction "SDA_3") (pintype "passive"))
      (node (ref "J9") (pin "3") (pinfunction "SDA_3") (pintype "passive"))
      (node (ref "Q1") (pin "2") (pinfunction "S_2") (pintype "passive"))
      (node (ref "R3") (pin "2") (pinfunction "2_2") (pintype "passive"))
    )
    (net (code "157") (name "VIN") (class "Default")
      (node (ref "J6") (pin "7") (pinfunction "7_7") (pintype "passive"))
      (node (ref "U1") (pin "VIN") (pinfunction "VIN_VIN") (pintype "bidirectional"))
    )
  )
)
